# 08_-_MCU.net
KiCad netlist of a schematic drawn in Altium Designer
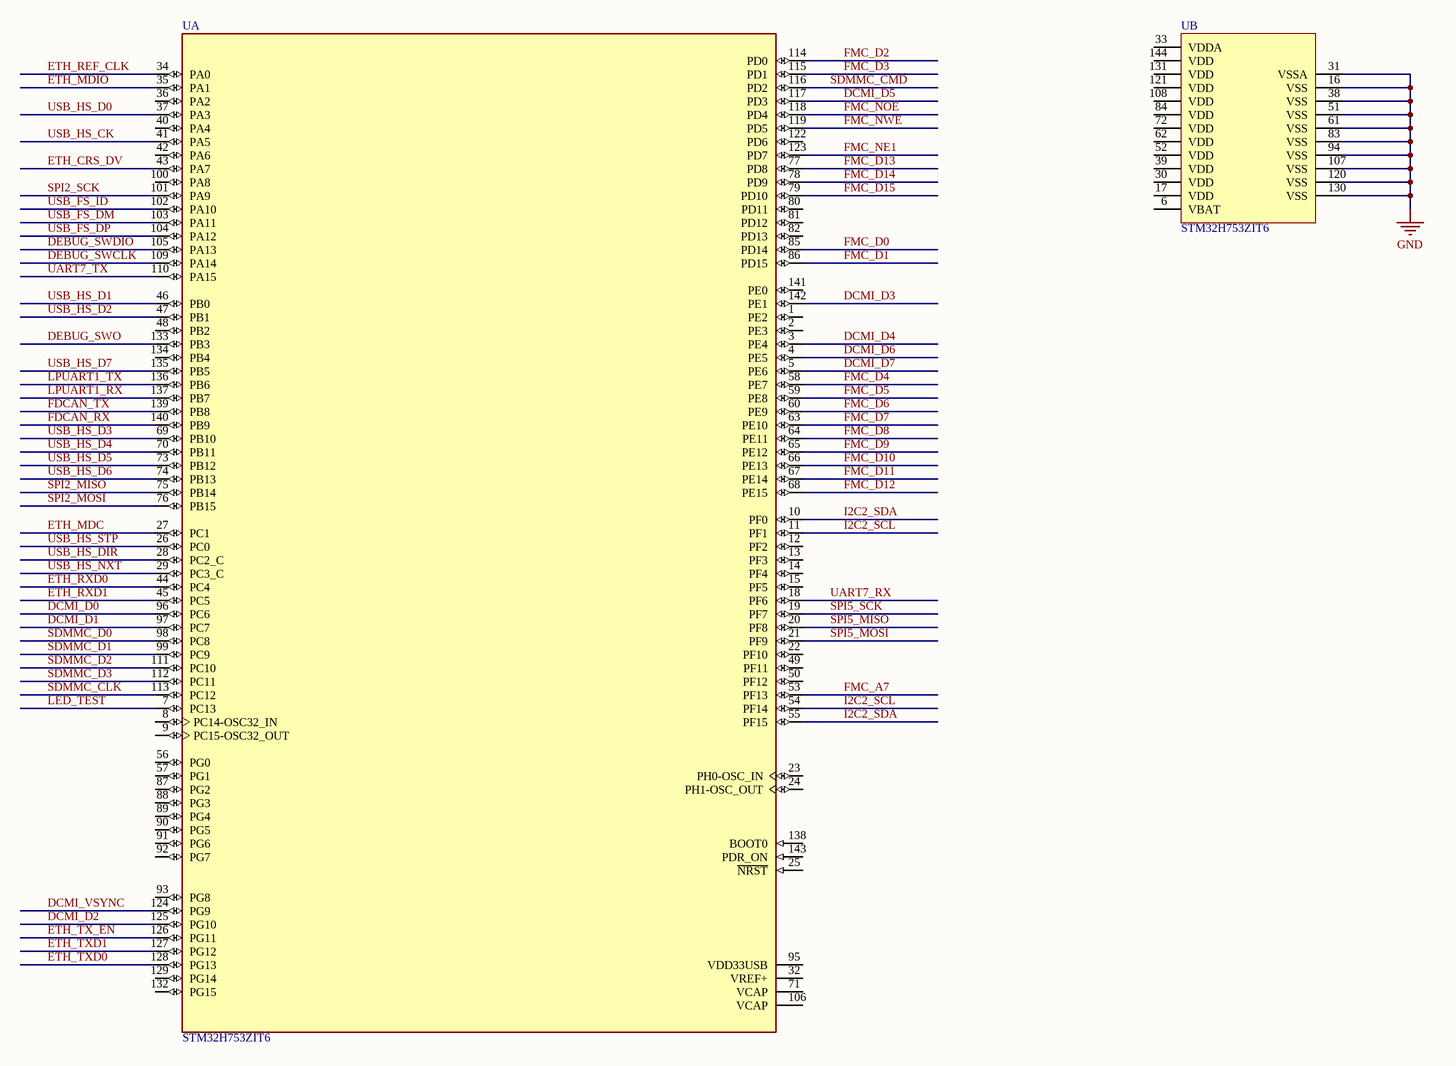
[diagram p0: [08] - MCU.SchDoc]

(export (version "E")
  (design (tool "Eeschema 10.0.6"))
  (components
    (comp (ref "U")
      (value "STM32H753ZIT6")
      (footprint "ST_MCU_STM32H753ZIT6_LQFP144")
      (description "ARMÂ® CortexÂ®-M7 STM32H7 Microcontroller IC 32-Bit 480MHz 2MB _2M x 8_ FLASH 144-LQFP _20x20_")
      (fields (field (name "MF") "STMicroelectronics"))
      (libsource (lib "TUNA_Altium_Lib") (part "STM32H753ZIT6"))
    )
  )
  (nets
    (net (code "1") (name "/DCMI_D0") (class "Default")
      (node (ref "U") (pin "96") (pinfunction "PC6_96") (pintype "bidirectional"))
    )
    (net (code "2") (name "/DCMI_D1") (class "Default")
      (node (ref "U") (pin "97") (pinfunction "PC7_97") (pintype "bidirectional"))
    )
    (net (code "3") (name "/DCMI_D2") (class "Default")
      (node (ref "U") (pin "125") (pinfunction "PG10_125") (pintype "bidirectional"))
    )
    (net (code "4") (name "/DCMI_D3") (class "Default")
      (node (ref "U") (pin "142") (pinfunction "PE1_142") (pintype "bidirectional"))
    )
    (net (code "5") (name "/DCMI_D4") (class "Default")
      (node (ref "U") (pin "3") (pinfunction "PE4_3") (pintype "bidirectional"))
    )
    (net (code "6") (name "/DCMI_D5") (class "Default")
      (node (ref "U") (pin "117") (pinfunction "PD3_117") (pintype "bidirectional"))
    )
    (net (code "7") (name "/DCMI_D6") (class "Default")
      (node (ref "U") (pin "4") (pinfunction "PE5_4") (pintype "bidirectional"))
    )
    (net (code "8") (name "/DCMI_D7") (class "Default")
      (node (ref "U") (pin "5") (pinfunction "PE6_5") (pintype "bidirectional"))
    )
    (net (code "9") (name "/DCMI_VSYNC") (class "Default")
      (node (ref "U") (pin "124") (pinfunction "PG9_124") (pintype "bidirectional"))
    )
    (net (code "10") (name "/DEBUG_SWCLK") (class "Default")
      (node (ref "U") (pin "109") (pinfunction "PA14_109") (pintype "bidirectional"))
    )
    (net (code "11") (name "/DEBUG_SWDIO") (class "Default")
      (node (ref "U") (pin "105") (pinfunction "PA13_105") (pintype "bidirectional"))
    )
    (net (code "12") (name "/DEBUG_SWO") (class "Default")
      (node (ref "U") (pin "133") (pinfunction "PB3_133") (pintype "bidirectional"))
    )
    (net (code "13") (name "/ETH_CRS_DV") (class "Default")
      (node (ref "U") (pin "43") (pinfunction "PA7_43") (pintype "bidirectional"))
    )
    (net (code "14") (name "/ETH_MDC") (class "Default")
      (node (ref "U") (pin "27") (pinfunction "PC1_27") (pintype "bidirectional"))
    )
    (net (code "15") (name "/ETH_MDIO") (class "Default")
      (node (ref "U") (pin "35") (pinfunction "PA1_35") (pintype "bidirectional"))
    )
    (net (code "16") (name "/ETH_REF_CLK") (class "Default")
      (node (ref "U") (pin "34") (pinfunction "PA0_34") (pintype "bidirectional"))
    )
    (net (code "17") (name "/ETH_RXD0") (class "Default")
      (node (ref "U") (pin "44") (pinfunction "PC4_44") (pintype "bidirectional"))
    )
    (net (code "18") (name "/ETH_RXD1") (class "Default")
      (node (ref "U") (pin "45") (pinfunction "PC5_45") (pintype "bidirectional"))
    )
    (net (code "19") (name "/ETH_TXD0") (class "Default")
      (node (ref "U") (pin "128") (pinfunction "PG13_128") (pintype "bidirectional"))
    )
    (net (code "20") (name "/ETH_TXD1") (class "Default")
      (node (ref "U") (pin "127") (pinfunction "PG12_127") (pintype "bidirectional"))
    )
    (net (code "21") (name "/ETH_TX_EN") (class "Default")
      (node (ref "U") (pin "126") (pinfunction "PG11_126") (pintype "bidirectional"))
    )
    (net (code "22") (name "/FDCAN_RX") (class "Default")
      (node (ref "U") (pin "140") (pinfunction "PB9_140") (pintype "bidirectional"))
    )
    (net (code "23") (name "/FDCAN_TX") (class "Default")
      (node (ref "U") (pin "139") (pinfunction "PB8_139") (pintype "bidirectional"))
    )
    (net (code "24") (name "/FMC_A7") (class "Default")
      (node (ref "U") (pin "53") (pinfunction "PF13_53") (pintype "bidirectional"))
    )
    (net (code "25") (name "/FMC_D0") (class "Default")
      (node (ref "U") (pin "85") (pinfunction "PD14_85") (pintype "bidirectional"))
    )
    (net (code "26") (name "/FMC_D1") (class "Default")
      (node (ref "U") (pin "86") (pinfunction "PD15_86") (pintype "bidirectional"))
    )
    (net (code "27") (name "/FMC_D2") (class "Default")
      (node (ref "U") (pin "114") (pinfunction "PD0_114") (pintype "bidirectional"))
    )
    (net (code "28") (name "/FMC_D3") (class "Default")
      (node (ref "U") (pin "115") (pinfunction "PD1_115") (pintype "bidirectional"))
    )
    (net (code "29") (name "/FMC_D4") (class "Default")
      (node (ref "U") (pin "58") (pinfunction "PE7_58") (pintype "bidirectional"))
    )
    (net (code "30") (name "/FMC_D5") (class "Default")
      (node (ref "U") (pin "59") (pinfunction "PE8_59") (pintype "bidirectional"))
    )
    (net (code "31") (name "/FMC_D6") (class "Default")
      (node (ref "U") (pin "60") (pinfunction "PE9_60") (pintype "bidirectional"))
    )
    (net (code "32") (name "/FMC_D7") (class "Default")
      (node (ref "U") (pin "63") (pinfunction "PE10_63") (pintype "bidirectional"))
    )
    (net (code "33") (name "/FMC_D8") (class "Default")
      (node (ref "U") (pin "64") (pinfunction "PE11_64") (pintype "bidirectional"))
    )
    (net (code "34") (name "/FMC_D9") (class "Default")
      (node (ref "U") (pin "65") (pinfunction "PE12_65") (pintype "bidirectional"))
    )
    (net (code "35") (name "/FMC_D10") (class "Default")
      (node (ref "U") (pin "66") (pinfunction "PE13_66") (pintype "bidirectional"))
    )
    (net (code "36") (name "/FMC_D11") (class "Default")
      (node (ref "U") (pin "67") (pinfunction "PE14_67") (pintype "bidirectional"))
    )
    (net (code "37") (name "/FMC_D12") (class "Default")
      (node (ref "U") (pin "68") (pinfunction "PE15_68") (pintype "bidirectional"))
    )
    (net (code "38") (name "/FMC_D13") (class "Default")
      (node (ref "U") (pin "77") (pinfunction "PD8_77") (pintype "bidirectional"))
    )
    (net (code "39") (name "/FMC_D14") (class "Default")
      (node (ref "U") (pin "78") (pinfunction "PD9_78") (pintype "bidirectional"))
    )
    (net (code "40") (name "/FMC_D15") (class "Default")
      (node (ref "U") (pin "79") (pinfunction "PD10_79") (pintype "bidirectional"))
    )
    (net (code "41") (name "/FMC_NE1") (class "Default")
      (node (ref "U") (pin "123") (pinfunction "PD7_123") (pintype "bidirectional"))
    )
    (net (code "42") (name "/FMC_NOE") (class "Default")
      (node (ref "U") (pin "118") (pinfunction "PD4_118") (pintype "bidirectional"))
    )
    (net (code "43") (name "/FMC_NWE") (class "Default")
      (node (ref "U") (pin "119") (pinfunction "PD5_119") (pintype "bidirectional"))
    )
    (net (code "44") (name "/I2C2_SCL") (class "Default")
      (node (ref "U") (pin "11") (pinfunction "PF1_11") (pintype "bidirectional"))
      (node (ref "U") (pin "54") (pinfunction "PF14_54") (pintype "bidirectional"))
    )
    (net (code "45") (name "/I2C2_SDA") (class "Default")
      (node (ref "U") (pin "10") (pinfunction "PF0_10") (pintype "bidirectional"))
      (node (ref "U") (pin "55") (pinfunction "PF15_55") (pintype "bidirectional"))
    )
    (net (code "46") (name "/LED_TEST") (class "Default")
      (node (ref "U") (pin "7") (pinfunction "PC13_7") (pintype "bidirectional"))
    )
    (net (code "47") (name "/LPUART1_RX") (class "Default")
      (node (ref "U") (pin "137") (pinfunction "PB7_137") (pintype "bidirectional"))
    )
    (net (code "48") (name "/LPUART1_TX") (class "Default")
      (node (ref "U") (pin "136") (pinfunction "PB6_136") (pintype "bidirectional"))
    )
    (net (code "49") (name "/SDMMC_CLK") (class "Default")
      (node (ref "U") (pin "113") (pinfunction "PC12_113") (pintype "bidirectional"))
    )
    (net (code "50") (name "/SDMMC_CMD") (class "Default")
      (node (ref "U") (pin "116") (pinfunction "PD2_116") (pintype "bidirectional"))
    )
    (net (code "51") (name "/SDMMC_D0") (class "Default")
      (node (ref "U") (pin "98") (pinfunction "PC8_98") (pintype "bidirectional"))
    )
    (net (code "52") (name "/SDMMC_D1") (class "Default")
      (node (ref "U") (pin "99") (pinfunction "PC9_99") (pintype "bidirectional"))
    )
    (net (code "53") (name "/SDMMC_D2") (class "Default")
      (node (ref "U") (pin "111") (pinfunction "PC10_111") (pintype "bidirectional"))
    )
    (net (code "54") (name "/SDMMC_D3") (class "Default")
      (node (ref "U") (pin "112") (pinfunction "PC11_112") (pintype "bidirectional"))
    )
    (net (code "55") (name "/SPI2_MISO") (class "Default")
      (node (ref "U") (pin "75") (pinfunction "PB14_75") (pintype "bidirectional"))
    )
    (net (code "56") (name "/SPI2_MOSI") (class "Default")
      (node (ref "U") (pin "76") (pinfunction "PB15_76") (pintype "bidirectional"))
    )
    (net (code "57") (name "/SPI2_SCK") (class "Default")
      (node (ref "U") (pin "101") (pinfunction "PA9_101") (pintype "bidirectional"))
    )
    (net (code "58") (name "/SPI5_MISO") (class "Default")
      (node (ref "U") (pin "20") (pinfunction "PF8_20") (pintype "bidirectional"))
    )
    (net (code "59") (name "/SPI5_MOSI") (class "Default")
      (node (ref "U") (pin "21") (pinfunction "PF9_21") (pintype "bidirectional"))
    )
    (net (code "60") (name "/SPI5_SCK") (class "Default")
      (node (ref "U") (pin "19") (pinfunction "PF7_19") (pintype "bidirectional"))
    )
    (net (code "61") (name "/UART7_RX") (class "Default")
      (node (ref "U") (pin "18") (pinfunction "PF6_18") (pintype "bidirectional"))
    )
    (net (code "62") (name "/UART7_TX") (class "Default")
      (node (ref "U") (pin "110") (pinfunction "PA15_110") (pintype "bidirectional"))
    )
    (net (code "63") (name "/USB_FS_DM") (class "Default")
      (node (ref "U") (pin "103") (pinfunction "PA11_103") (pintype "bidirectional"))
    )
    (net (code "64") (name "/USB_FS_DP") (class "Default")
      (node (ref "U") (pin "104") (pinfunction "PA12_104") (pintype "bidirectional"))
    )
    (net (code "65") (name "/USB_FS_ID") (class "Default")
      (node (ref "U") (pin "102") (pinfunction "PA10_102") (pintype "bidirectional"))
    )
    (net (code "66") (name "/USB_HS_CK") (class "Default")
      (node (ref "U") (pin "41") (pinfunction "PA5_41") (pintype "bidirectional"))
    )
    (net (code "67") (name "/USB_HS_D0") (class "Default")
      (node (ref "U") (pin "37") (pinfunction "PA3_37") (pintype "bidirectional"))
    )
    (net (code "68") (name "/USB_HS_D1") (class "Default")
      (node (ref "U") (pin "46") (pinfunction "PB0_46") (pintype "bidirectional"))
    )
    (net (code "69") (name "/USB_HS_D2") (class "Default")
      (node (ref "U") (pin "47") (pinfunction "PB1_47") (pintype "bidirectional"))
    )
    (net (code "70") (name "/USB_HS_D3") (class "Default")
      (node (ref "U") (pin "69") (pinfunction "PB10_69") (pintype "bidirectional"))
    )
    (net (code "71") (name "/USB_HS_D4") (class "Default")
      (node (ref "U") (pin "70") (pinfunction "PB11_70") (pintype "bidirectional"))
    )
    (net (code "72") (name "/USB_HS_D5") (class "Default")
      (node (ref "U") (pin "73") (pinfunction "PB12_73") (pintype "bidirectional"))
    )
    (net (code "73") (name "/USB_HS_D6") (class "Default")
      (node (ref "U") (pin "74") (pinfunction "PB13_74") (pintype "bidirectional"))
    )
    (net (code "74") (name "/USB_HS_D7") (class "Default")
      (node (ref "U") (pin "135") (pinfunction "PB5_135") (pintype "bidirectional"))
    )
    (net (code "75") (name "/USB_HS_DIR") (class "Default")
      (node (ref "U") (pin "28") (pinfunction "PC2_C_28") (pintype "bidirectional"))
    )
    (net (code "76") (name "/USB_HS_NXT") (class "Default")
      (node (ref "U") (pin "29") (pinfunction "PC3_C_29") (pintype "bidirectional"))
    )
    (net (code "77") (name "/USB_HS_STP") (class "Default")
      (node (ref "U") (pin "26") (pinfunction "PC0_26") (pintype "bidirectional"))
    )
    (net (code "78") (name "GND") (class "Default")
      (node (ref "U") (pin "107") (pinfunction "VSS_107") (pintype "power_in"))
      (node (ref "U") (pin "120") (pinfunction "VSS_120") (pintype "power_in"))
      (node (ref "U") (pin "130") (pinfunction "VSS_130") (pintype "power_in"))
      (node (ref "U") (pin "16") (pinfunction "VSS_16") (pintype "power_in"))
      (node (ref "U") (pin "31") (pinfunction "VSSA_31") (pintype "power_in"))
      (node (ref "U") (pin "38") (pinfunction "VSS_38") (pintype "power_in"))
      (node (ref "U") (pin "51") (pinfunction "VSS_51") (pintype "power_in"))
      (node (ref "U") (pin "61") (pinfunction "VSS_61") (pintype "power_in"))
      (node (ref "U") (pin "83") (pinfunction "VSS_83") (pintype "power_in"))
      (node (ref "U") (pin "94") (pinfunction "VSS_94") (pintype "power_in"))
    )
    (net (code "79") (name "unconnected-(UA-BOOT0-Pad138)") (class "Default")
      (node (ref "U") (pin "138") (pinfunction "BOOT0_138") (pintype "input"))
    )
    (net (code "80") (name "unconnected-(UA-PA2-Pad36)") (class "Default")
      (node (ref "U") (pin "36") (pinfunction "PA2_36") (pintype "bidirectional"))
    )
    (net (code "81") (name "unconnected-(UA-PA4-Pad40)") (class "Default")
      (node (ref "U") (pin "40") (pinfunction "PA4_40") (pintype "bidirectional"))
    )
    (net (code "82") (name "unconnected-(UA-PA6-Pad42)") (class "Default")
      (node (ref "U") (pin "42") (pinfunction "PA6_42") (pintype "bidirectional"))
    )
    (net (code "83") (name "unconnected-(UA-PA8-Pad100)") (class "Default")
      (node (ref "U") (pin "100") (pinfunction "PA8_100") (pintype "bidirectional"))
    )
    (net (code "84") (name "unconnected-(UA-PB2-Pad48)") (class "Default")
      (node (ref "U") (pin "48") (pinfunction "PB2_48") (pintype "bidirectional"))
    )
    (net (code "85") (name "unconnected-(UA-PB4-Pad134)") (class "Default")
      (node (ref "U") (pin "134") (pinfunction "PB4_134") (pintype "bidirectional"))
    )
    (net (code "86") (name "unconnected-(UA-PC14-OSC32_IN-Pad8)") (class "Default")
      (node (ref "U") (pin "8") (pinfunction "PC14-OSC32_IN_8") (pintype "bidirectional"))
    )
    (net (code "87") (name "unconnected-(UA-PC15-OSC32_OUT-Pad9)") (class "Default")
      (node (ref "U") (pin "9") (pinfunction "PC15-OSC32_OUT_9") (pintype "bidirectional"))
    )
    (net (code "88") (name "unconnected-(UA-PD6-Pad122)") (class "Default")
      (node (ref "U") (pin "122") (pinfunction "PD6_122") (pintype "bidirectional"))
    )
    (net (code "89") (name "unconnected-(UA-PD11-Pad80)") (class "Default")
      (node (ref "U") (pin "80") (pinfunction "PD11_80") (pintype "bidirectional"))
    )
    (net (code "90") (name "unconnected-(UA-PD12-Pad81)") (class "Default")
      (node (ref "U") (pin "81") (pinfunction "PD12_81") (pintype "bidirectional"))
    )
    (net (code "91") (name "unconnected-(UA-PD13-Pad82)") (class "Default")
      (node (ref "U") (pin "82") (pinfunction "PD13_82") (pintype "bidirectional"))
    )
    (net (code "92") (name "unconnected-(UA-PDR_ON-Pad143)") (class "Default")
      (node (ref "U") (pin "143") (pinfunction "PDR_ON_143") (pintype "input"))
    )
    (net (code "93") (name "unconnected-(UA-PE0-Pad141)") (class "Default")
      (node (ref "U") (pin "141") (pinfunction "PE0_141") (pintype "bidirectional"))
    )
    (net (code "94") (name "unconnected-(UA-PE2-Pad1)") (class "Default")
      (node (ref "U") (pin "1") (pinfunction "PE2_1") (pintype "bidirectional"))
    )
    (net (code "95") (name "unconnected-(UA-PE3-Pad2)") (class "Default")
      (node (ref "U") (pin "2") (pinfunction "PE3_2") (pintype "bidirectional"))
    )
    (net (code "96") (name "unconnected-(UA-PF2-Pad12)") (class "Default")
      (node (ref "U") (pin "12") (pinfunction "PF2_12") (pintype "bidirectional"))
    )
    (net (code "97") (name "unconnected-(UA-PF3-Pad13)") (class "Default")
      (node (ref "U") (pin "13") (pinfunction "PF3_13") (pintype "bidirectional"))
    )
    (net (code "98") (name "unconnected-(UA-PF4-Pad14)") (class "Default")
      (node (ref "U") (pin "14") (pinfunction "PF4_14") (pintype "bidirectional"))
    )
    (net (code "99") (name "unconnected-(UA-PF5-Pad15)") (class "Default")
      (node (ref "U") (pin "15") (pinfunction "PF5_15") (pintype "bidirectional"))
    )
    (net (code "100") (name "unconnected-(UA-PF10-Pad22)") (class "Default")
      (node (ref "U") (pin "22") (pinfunction "PF10_22") (pintype "bidirectional"))
    )
    (net (code "101") (name "unconnected-(UA-PF11-Pad49)") (class "Default")
      (node (ref "U") (pin "49") (pinfunction "PF11_49") (pintype "bidirectional"))
    )
    (net (code "102") (name "unconnected-(UA-PF12-Pad50)") (class "Default")
      (node (ref "U") (pin "50") (pinfunction "PF12_50") (pintype "bidirectional"))
    )
    (net (code "103") (name "unconnected-(UA-PG0-Pad56)") (class "Default")
      (node (ref "U") (pin "56") (pinfunction "PG0_56") (pintype "bidirectional"))
    )
    (net (code "104") (name "unconnected-(UA-PG1-Pad57)") (class "Default")
      (node (ref "U") (pin "57") (pinfunction "PG1_57") (pintype "bidirectional"))
    )
    (net (code "105") (name "unconnected-(UA-PG2-Pad87)") (class "Default")
      (node (ref "U") (pin "87") (pinfunction "PG2_87") (pintype "bidirectional"))
    )
    (net (code "106") (name "unconnected-(UA-PG3-Pad88)") (class "Default")
      (node (ref "U") (pin "88") (pinfunction "PG3_88") (pintype "bidirectional"))
    )
    (net (code "107") (name "unconnected-(UA-PG4-Pad89)") (class "Default")
      (node (ref "U") (pin "89") (pinfunction "PG4_89") (pintype "bidirectional"))
    )
    (net (code "108") (name "unconnected-(UA-PG5-Pad90)") (class "Default")
      (node (ref "U") (pin "90") (pinfunction "PG5_90") (pintype "bidirectional"))
    )
    (net (code "109") (name "unconnected-(UA-PG6-Pad91)") (class "Default")
      (node (ref "U") (pin "91") (pinfunction "PG6_91") (pintype "bidirectional"))
    )
    (net (code "110") (name "unconnected-(UA-PG7-Pad92)") (class "Default")
      (node (ref "U") (pin "92") (pinfunction "PG7_92") (pintype "bidirectional"))
    )
    (net (code "111") (name "unconnected-(UA-PG8-Pad93)") (class "Default")
      (node (ref "U") (pin "93") (pinfunction "PG8_93") (pintype "bidirectional"))
    )
    (net (code "112") (name "unconnected-(UA-PG14-Pad129)") (class "Default")
      (node (ref "U") (pin "129") (pinfunction "PG14_129") (pintype "bidirectional"))
    )
    (net (code "113") (name "unconnected-(UA-PG15-Pad132)") (class "Default")
      (node (ref "U") (pin "132") (pinfunction "PG15_132") (pintype "bidirectional"))
    )
    (net (code "114") (name "unconnected-(UA-PH0-OSC_IN-Pad23)") (class "Default")
      (node (ref "U") (pin "23") (pinfunction "PH0-OSC_IN_23") (pintype "bidirectional"))
    )
    (net (code "115") (name "unconnected-(UA-PH1-OSC_OUT-Pad24)") (class "Default")
      (node (ref "U") (pin "24") (pinfunction "PH1-OSC_OUT_24") (pintype "bidirectional"))
    )
    (net (code "116") (name "unconnected-(UA-VCAP-Pad71)") (class "Default")
      (node (ref "U") (pin "71") (pinfunction "VCAP_71") (pintype "power_in"))
    )
    (net (code "117") (name "unconnected-(UA-VCAP-Pad106)") (class "Default")
      (node (ref "U") (pin "106") (pinfunction "VCAP_106") (pintype "power_in"))
    )
    (net (code "118") (name "unconnected-(UA-VDD33USB-Pad95)") (class "Default")
      (node (ref "U") (pin "95") (pinfunction "VDD33USB_95") (pintype "power_in"))
    )
    (net (code "119") (name "unconnected-(UA-VREF+-Pad32)") (class "Default")
      (node (ref "U") (pin "32") (pinfunction "VREF+_32") (pintype "power_in"))
    )
    (net (code "120") (name "unconnected-(UA-~{NRST}-Pad25)") (class "Default")
      (node (ref "U") (pin "25") (pinfunction "~{NRST}_25") (pintype "input"))
    )
    (net (code "121") (name "unconnected-(UB-VBAT-Pad6)") (class "Default")
      (node (ref "U") (pin "6") (pinfunction "VBAT_6") (pintype "power_in"))
    )
    (net (code "122") (name "unconnected-(UB-VDD-Pad17)") (class "Default")
      (node (ref "U") (pin "17") (pinfunction "VDD_17") (pintype "power_in"))
    )
    (net (code "123") (name "unconnected-(UB-VDD-Pad30)") (class "Default")
      (node (ref "U") (pin "30") (pinfunction "VDD_30") (pintype "power_in"))
    )
    (net (code "124") (name "unconnected-(UB-VDD-Pad39)") (class "Default")
      (node (ref "U") (pin "39") (pinfunction "VDD_39") (pintype "power_in"))
    )
    (net (code "125") (name "unconnected-(UB-VDD-Pad52)") (class "Default")
      (node (ref "U") (pin "52") (pinfunction "VDD_52") (pintype "power_in"))
    )
    (net (code "126") (name "unconnected-(UB-VDD-Pad62)") (class "Default")
      (node (ref "U") (pin "62") (pinfunction "VDD_62") (pintype "power_in"))
    )
    (net (code "127") (name "unconnected-(UB-VDD-Pad72)") (class "Default")
      (node (ref "U") (pin "72") (pinfunction "VDD_72") (pintype "power_in"))
    )
    (net (code "128") (name "unconnected-(UB-VDD-Pad84)") (class "Default")
      (node (ref "U") (pin "84") (pinfunction "VDD_84") (pintype "power_in"))
    )
    (net (code "129") (name "unconnected-(UB-VDD-Pad108)") (class "Default")
      (node (ref "U") (pin "108") (pinfunction "VDD_108") (pintype "power_in"))
    )
    (net (code "130") (name "unconnected-(UB-VDD-Pad121)") (class "Default")
      (node (ref "U") (pin "121") (pinfunction "VDD_121") (pintype "power_in"))
    )
    (net (code "131") (name "unconnected-(UB-VDD-Pad131)") (class "Default")
      (node (ref "U") (pin "131") (pinfunction "VDD_131") (pintype "power_in"))
    )
    (net (code "132") (name "unconnected-(UB-VDD-Pad144)") (class "Default")
      (node (ref "U") (pin "144") (pinfunction "VDD_144") (pintype "power_in"))
    )
    (net (code "133") (name "unconnected-(UB-VDDA-Pad33)") (class "Default")
      (node (ref "U") (pin "33") (pinfunction "VDDA_33") (pintype "power_in"))
    )
  )
)
